# USB-C_breakout.net
KiCad netlist of a schematic drawn in EAGLE
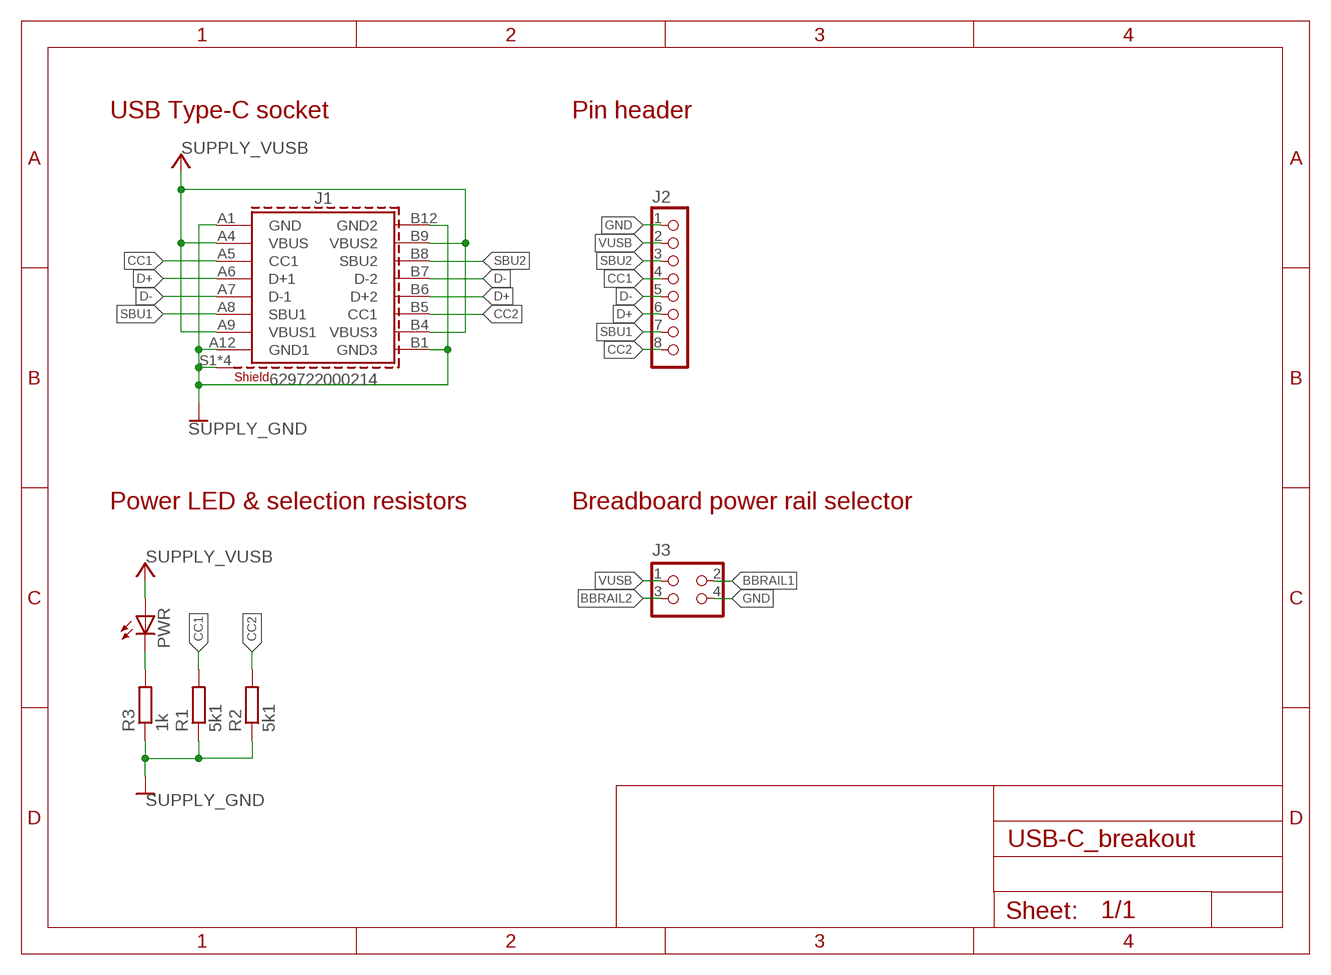
[diagram p0: schematic, sheet 1]

(export (version "E")
  (design (tool "Eeschema 10.0.6"))
  (components
    (comp (ref "J1")
      (value "629722000214")
      (footprint "eagle-import:629722000214")
      (libsource (lib "eagle-import") (part "629722000214"))
    )
    (comp (ref "J2")
      (value "CON_HEADER_1X08-PTH")
      (footprint "eagle-import:M1X8")
      (libsource (lib "eagle-import") (part "CON_HEADER_1X08-PTH"))
    )
    (comp (ref "J3")
      (value "CON_HEADER_2X02-PTH")
      (footprint "eagle-import:M2X2")
      (libsource (lib "eagle-import") (part "CON_HEADER_2X02-PTH"))
    )
    (comp (ref "PWR")
      (value "LED-0603")
      (footprint "eagle-import:LED-603")
      (libsource (lib "eagle-import") (part "LED-0603"))
    )
    (comp (ref "R1")
      (value "5k1")
      (footprint "eagle-import:R603")
      (libsource (lib "eagle-import") (part "RESISTOR-0603"))
    )
    (comp (ref "R2")
      (value "5k1")
      (footprint "eagle-import:R603")
      (libsource (lib "eagle-import") (part "RESISTOR-0603"))
    )
    (comp (ref "R3")
      (value "1k")
      (footprint "eagle-import:R603")
      (libsource (lib "eagle-import") (part "RESISTOR-0603"))
    )
  )
  (nets
    (net (code "1") (name "BBRAIL1") (class "Default")
      (node (ref "J3") (pin "2") (pinfunction "2_2") (pintype "passive"))
    )
    (net (code "2") (name "BBRAIL2") (class "Default")
      (node (ref "J3") (pin "3") (pinfunction "3_3") (pintype "passive"))
    )
    (net (code "3") (name "CC1") (class "Default")
      (node (ref "J1") (pin "A5") (pinfunction "CC1_A5") (pintype "passive"))
      (node (ref "J2") (pin "4") (pinfunction "4_4") (pintype "passive"))
      (node (ref "R1") (pin "2") (pinfunction "2_2") (pintype "passive"))
    )
    (net (code "4") (name "CC2") (class "Default")
      (node (ref "J1") (pin "B5") (pinfunction "CC1_B5") (pintype "passive"))
      (node (ref "J2") (pin "8") (pinfunction "8_8") (pintype "passive"))
      (node (ref "R2") (pin "2") (pinfunction "2_2") (pintype "passive"))
    )
    (net (code "5") (name "D+") (class "Default")
      (node (ref "J1") (pin "A6") (pinfunction "D+1_A6") (pintype "passive"))
      (node (ref "J1") (pin "B6") (pinfunction "D+2_B6") (pintype "passive"))
      (node (ref "J2") (pin "6") (pinfunction "6_6") (pintype "passive"))
    )
    (net (code "6") (name "D-") (class "Default")
      (node (ref "J1") (pin "A7") (pinfunction "D-1_A7") (pintype "passive"))
      (node (ref "J1") (pin "B7") (pinfunction "D-2_B7") (pintype "passive"))
      (node (ref "J2") (pin "5") (pinfunction "5_5") (pintype "passive"))
    )
    (net (code "7") (name "GND") (class "Default")
      (node (ref "J1") (pin "A1") (pinfunction "GND_A1") (pintype "passive"))
      (node (ref "J1") (pin "A12") (pinfunction "GND1_A12") (pintype "passive"))
      (node (ref "J1") (pin "B1") (pinfunction "GND3_B1") (pintype "passive"))
      (node (ref "J1") (pin "B12") (pinfunction "GND2_B12") (pintype "passive"))
      (node (ref "J1") (pin "S1") (pinfunction "SHIELD_S1") (pintype "passive"))
      (node (ref "J1") (pin "S2") (pinfunction "SHIELD_S2") (pintype "passive"))
      (node (ref "J1") (pin "S3") (pinfunction "SHIELD_S3") (pintype "passive"))
      (node (ref "J1") (pin "S4") (pinfunction "SHIELD_S4") (pintype "passive"))
      (node (ref "J2") (pin "1") (pinfunction "1_1") (pintype "passive"))
      (node (ref "J3") (pin "4") (pinfunction "4_4") (pintype "passive"))
      (node (ref "R1") (pin "1") (pinfunction "1_1") (pintype "passive"))
      (node (ref "R2") (pin "1") (pinfunction "1_1") (pintype "passive"))
      (node (ref "R3") (pin "1") (pinfunction "1_1") (pintype "passive"))
    )
    (net (code "8") (name "Net-(PWR-PadC)") (class "Default")
      (node (ref "PWR") (pin "C") (pinfunction "C_C") (pintype "passive"))
      (node (ref "R3") (pin "2") (pinfunction "2_2") (pintype "passive"))
    )
    (net (code "9") (name "SBU1") (class "Default")
      (node (ref "J1") (pin "A8") (pinfunction "SBU1_A8") (pintype "passive"))
      (node (ref "J2") (pin "7") (pinfunction "7_7") (pintype "passive"))
    )
    (net (code "10") (name "SBU2") (class "Default")
      (node (ref "J1") (pin "B8") (pinfunction "SBU2_B8") (pintype "passive"))
      (node (ref "J2") (pin "3") (pinfunction "3_3") (pintype "passive"))
    )
    (net (code "11") (name "VUSB") (class "Default")
      (node (ref "J1") (pin "A4") (pinfunction "VBUS_A4") (pintype "passive"))
      (node (ref "J1") (pin "A9") (pinfunction "VBUS1_A9") (pintype "passive"))
      (node (ref "J1") (pin "B4") (pinfunction "VBUS3_B4") (pintype "passive"))
      (node (ref "J1") (pin "B9") (pinfunction "VBUS2_B9") (pintype "passive"))
      (node (ref "J2") (pin "2") (pinfunction "2_2") (pintype "passive"))
      (node (ref "J3") (pin "1") (pinfunction "1_1") (pintype "passive"))
      (node (ref "PWR") (pin "A") (pinfunction "A_A") (pintype "passive"))
    )
  )
)
